# SinglePhaseDriver_BLDCV5.net
KiCad netlist of a schematic drawn in EasyEDA Pro
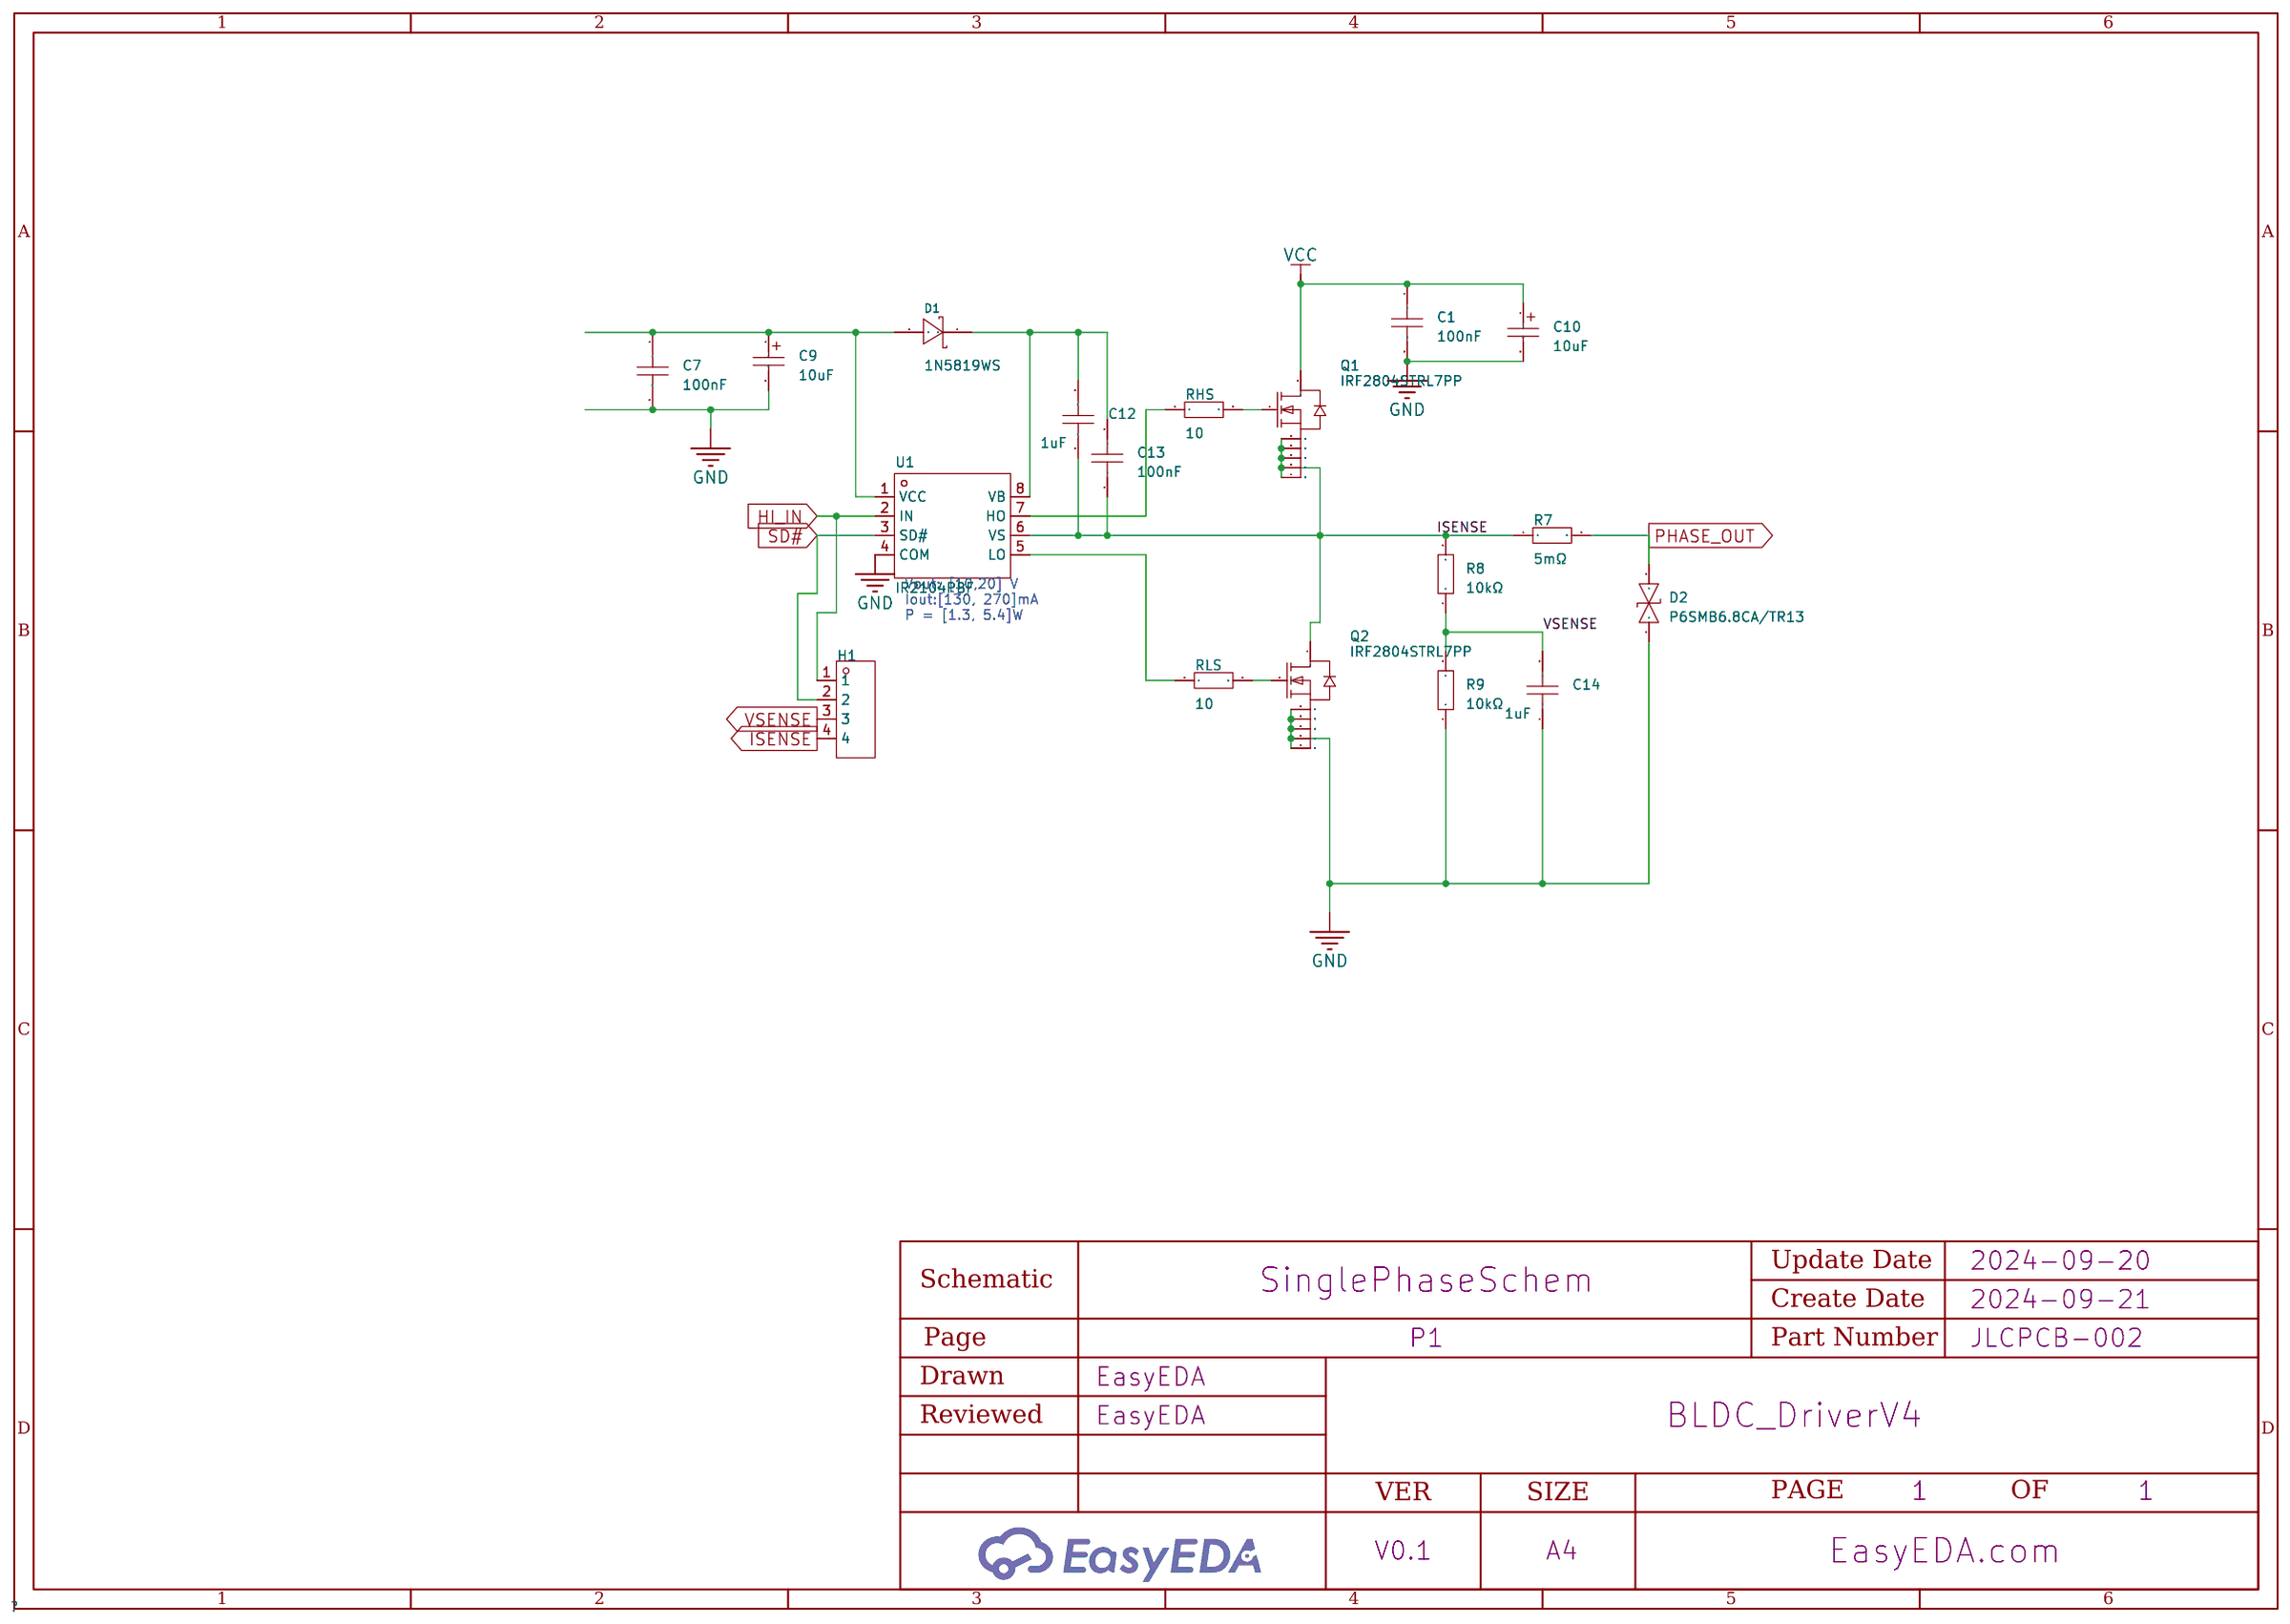
[diagram p0: schematic sheet]

(export (version "E")
  (design (tool "Eeschema 10.0.6"))
  (components
    (comp (ref "C1")
      (value "100nF")
      (footprint "easyedapro:C0603")
      (libsource (lib "easyedapro") (part "CAP"))
    )
    (comp (ref "C7")
      (value "100nF")
      (footprint "easyedapro:C0603")
      (libsource (lib "easyedapro") (part "CAP"))
    )
    (comp (ref "C9")
      (value "10uF")
      (footprint "easyedapro:CAP-SMD_BD5.0-L5.3-W5.3-LS6.3-FD")
      (libsource (lib "easyedapro") (part "C_Ele_SMD"))
    )
    (comp (ref "C10")
      (value "10uF")
      (footprint "easyedapro:CAP-SMD_BD5.0-L5.3-W5.3-LS6.3-FD")
      (libsource (lib "easyedapro") (part "C_Ele_SMD"))
    )
    (comp (ref "C12")
      (value "1uF")
      (footprint "easyedapro:CAP-TH_L7.2-W2.5-P5.00-D0.6")
      (fields (field (name "Manufacturer Part") "SMEC334J100M2") (field (name "Manufacturer") "CHAMPION(全鹏)"))
      (libsource (lib "easyedapro") (part "SMEC334J100M2"))
    )
    (comp (ref "C13")
      (value "100nF")
      (footprint "easyedapro:C0603")
      (libsource (lib "easyedapro") (part "CAP"))
    )
    (comp (ref "C14")
      (value "1uF")
      (footprint "easyedapro:CAP-TH_L7.2-W2.5-P5.00-D0.6")
      (fields (field (name "Manufacturer Part") "SMEC334J100M2") (field (name "Manufacturer") "CHAMPION(全鹏)"))
      (libsource (lib "easyedapro") (part "SMEC334J100M2"))
    )
    (comp (ref "D1")
      (value "1N5819WS")
      (footprint "easyedapro:SOD-323_L1.8-W1.3-LS2.5-RD")
      (description "Forward Voltage (Vf@If):600mV@1A Reverse Voltage (Vr):40V Average Rectified Current (Io):1A")
      (fields (field (name "Manufacturer") "Hottech(合科泰)"))
      (libsource (lib "easyedapro") (part "1N5819WS"))
    )
    (comp (ref "D2")
      (value "P6SMB6.8CA/TR13")
      (footprint "easyedapro:SMB_L4.6-W3.6-LS5.3-BI")
      (fields (field (name "Manufacturer") "Brightking(君耀电子)"))
      (libsource (lib "easyedapro") (part "P6SMB6.8CA-C78395"))
    )
    (comp (ref "H1")
      (value "~")
      (footprint "easyedapro:HDR-TH_4P-P2.54-V-M")
      (libsource (lib "easyedapro") (part "PZ254V-11-04P"))
    )
    (comp (ref "Q1")
      (value "IRF2804STRL7PP")
      (footprint "easyedapro:D2PAK-7_L10.6-W9.6-P1.27-LS15.9-BR")
      (fields (field (name "Manufacturer") "Infineon(英飞凌)"))
      (libsource (lib "easyedapro") (part "IRF2804STRL7PP"))
    )
    (comp (ref "Q2")
      (value "IRF2804STRL7PP")
      (footprint "easyedapro:D2PAK-7_L10.6-W9.6-P1.27-LS15.9-BR")
      (fields (field (name "Manufacturer") "Infineon(英飞凌)"))
      (libsource (lib "easyedapro") (part "IRF2804STRL7PP"))
    )
    (comp (ref "R7")
      (value "5mΩ")
      (footprint "easyedapro:R2512")
      (fields
        (field (name "Manufacturer Part") "PA2512FKF7W0R005E")
        (field (name "Manufacturer") "YAGEO(国巨)")
      )
      (libsource (lib "easyedapro") (part "PA2512FKF7W0R005L"))
    )
    (comp (ref "R8")
      (value "10kΩ")
      (footprint "easyedapro:R1210")
      (libsource (lib "easyedapro") (part "Res"))
    )
    (comp (ref "R9")
      (value "10kΩ")
      (footprint "easyedapro:R1210")
      (libsource (lib "easyedapro") (part "Res"))
    )
    (comp (ref "RHS") (value "10") (footprint "easyedapro:R1210") (libsource (lib "easyedapro") (part "Res")))
    (comp (ref "RLS") (value "10") (footprint "easyedapro:R1210") (libsource (lib "easyedapro") (part "Res")))
    (comp (ref "U1")
      (value "IR2104PBF")
      (footprint "easyedapro:DIP-8_L9.9-W6.6-P2.54-LS7.62-BL")
      (fields (field (name "Manufacturer") "Infineon(英飞凌)"))
      (libsource (lib "easyedapro") (part "IR2104PBF"))
    )
  )
  (nets
    (net (code "1") (name "GND") (class "Default")
      (node (ref "C1") (pin "2") (pinfunction "2_2") (pintype "input"))
      (node (ref "C10") (pin "2") (pinfunction "2_2") (pintype "input"))
      (node (ref "C14") (pin "1") (pinfunction "1_1") (pintype "input"))
      (node (ref "C7") (pin "2") (pinfunction "2_2") (pintype "input"))
      (node (ref "C9") (pin "2") (pinfunction "2_2") (pintype "input"))
      (node (ref "D2") (pin "1") (pinfunction "1_1") (pintype "unspecified"))
      (node (ref "Q2") (pin "2") (pinfunction "S_2") (pintype "unspecified"))
      (node (ref "Q2") (pin "3") (pinfunction "S_3") (pintype "unspecified"))
      (node (ref "Q2") (pin "5") (pinfunction "S_5") (pintype "unspecified"))
      (node (ref "Q2") (pin "6") (pinfunction "S_6") (pintype "unspecified"))
      (node (ref "Q2") (pin "7") (pinfunction "S_7") (pintype "unspecified"))
      (node (ref "R9") (pin "1") (pinfunction "1_1") (pintype "input"))
      (node (ref "U1") (pin "4") (pinfunction "COM_4") (pintype "unspecified"))
    )
    (net (code "2") (name "HI_IN") (class "Default")
      (node (ref "H1") (pin "1") (pinfunction "1_1") (pintype "unspecified"))
      (node (ref "U1") (pin "2") (pinfunction "IN_2") (pintype "unspecified"))
    )
    (net (code "3") (name "ISENSE") (class "Default")
      (node (ref "C12") (pin "1") (pinfunction "1_1") (pintype "input"))
      (node (ref "C13") (pin "2") (pinfunction "2_2") (pintype "input"))
      (node (ref "H1") (pin "4") (pinfunction "4_4") (pintype "unspecified"))
      (node (ref "Q1") (pin "2") (pinfunction "S_2") (pintype "unspecified"))
      (node (ref "Q1") (pin "3") (pinfunction "S_3") (pintype "unspecified"))
      (node (ref "Q1") (pin "5") (pinfunction "S_5") (pintype "unspecified"))
      (node (ref "Q1") (pin "6") (pinfunction "S_6") (pintype "unspecified"))
      (node (ref "Q1") (pin "7") (pinfunction "S_7") (pintype "unspecified"))
      (node (ref "Q2") (pin "4") (pinfunction "D_4") (pintype "unspecified"))
      (node (ref "R7") (pin "1") (pinfunction "1_1") (pintype "unspecified"))
      (node (ref "R8") (pin "2") (pinfunction "2_2") (pintype "input"))
      (node (ref "U1") (pin "6") (pinfunction "VS_6") (pintype "unspecified"))
    )
    (net (code "4") (name "Net-(D1-A)") (class "Default")
      (node (ref "C7") (pin "1") (pinfunction "1_1") (pintype "input"))
      (node (ref "C9") (pin "1") (pinfunction "1_1") (pintype "input"))
      (node (ref "D1") (pin "2") (pinfunction "A_2") (pintype "input"))
      (node (ref "U1") (pin "1") (pinfunction "VCC_1") (pintype "unspecified"))
    )
    (net (code "5") (name "Net-(D1-K)") (class "Default")
      (node (ref "C12") (pin "2") (pinfunction "2_2") (pintype "input"))
      (node (ref "C13") (pin "1") (pinfunction "1_1") (pintype "input"))
      (node (ref "D1") (pin "1") (pinfunction "K_1") (pintype "input"))
      (node (ref "U1") (pin "8") (pinfunction "VB_8") (pintype "unspecified"))
    )
    (net (code "6") (name "Net-(Q1-G)") (class "Default")
      (node (ref "Q1") (pin "1") (pinfunction "G_1") (pintype "unspecified"))
      (node (ref "RHS") (pin "2") (pinfunction "2_2") (pintype "input"))
    )
    (net (code "7") (name "Net-(Q2-G)") (class "Default")
      (node (ref "Q2") (pin "1") (pinfunction "G_1") (pintype "unspecified"))
      (node (ref "RLS") (pin "2") (pinfunction "2_2") (pintype "input"))
    )
    (net (code "8") (name "Net-(U1-HO)") (class "Default")
      (node (ref "RHS") (pin "1") (pinfunction "1_1") (pintype "input"))
      (node (ref "U1") (pin "7") (pinfunction "HO_7") (pintype "unspecified"))
    )
    (net (code "9") (name "Net-(U1-LO)") (class "Default")
      (node (ref "RLS") (pin "1") (pinfunction "1_1") (pintype "input"))
      (node (ref "U1") (pin "5") (pinfunction "LO_5") (pintype "unspecified"))
    )
    (net (code "10") (name "PHASE_OUT") (class "Default")
      (node (ref "D2") (pin "2") (pinfunction "2_2") (pintype "unspecified"))
      (node (ref "R7") (pin "2") (pinfunction "2_2") (pintype "unspecified"))
    )
    (net (code "11") (name "SD#") (class "Default")
      (node (ref "H1") (pin "2") (pinfunction "2_2") (pintype "unspecified"))
      (node (ref "U1") (pin "3") (pinfunction "SD#_3") (pintype "unspecified"))
    )
    (net (code "12") (name "VCC") (class "Default")
      (node (ref "C1") (pin "1") (pinfunction "1_1") (pintype "input"))
      (node (ref "C10") (pin "1") (pinfunction "1_1") (pintype "input"))
      (node (ref "Q1") (pin "4") (pinfunction "D_4") (pintype "unspecified"))
    )
    (net (code "13") (name "VSENSE") (class "Default")
      (node (ref "C14") (pin "2") (pinfunction "2_2") (pintype "input"))
      (node (ref "H1") (pin "3") (pinfunction "3_3") (pintype "unspecified"))
      (node (ref "R8") (pin "1") (pinfunction "1_1") (pintype "input"))
      (node (ref "R9") (pin "2") (pinfunction "2_2") (pintype "input"))
    )
  )
)
